# usb-gamepad.net
KiCad netlist of a schematic drawn in EAGLE
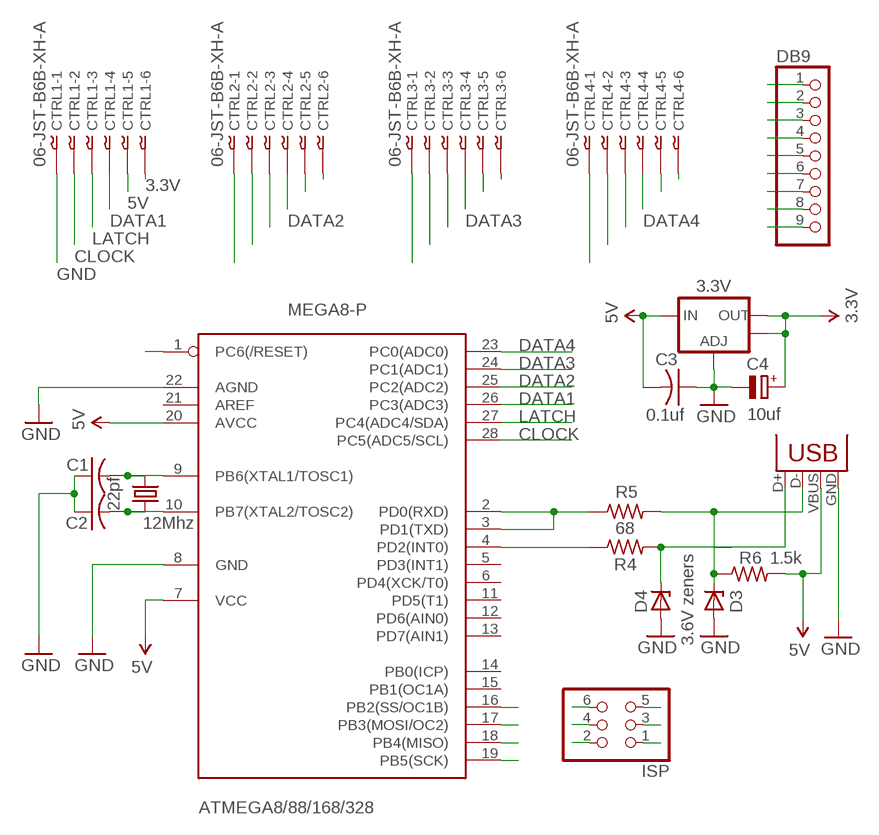
[diagram p0: schematic, sheet 1]

(export (version "E")
  (design (tool "Eeschema 10.0.6"))
  (components
    (comp (ref "3.3V")
      (value "V_REG_LM1117SOT223")
      (footprint "eagle-import:SOT223")
      (libsource (lib "eagle-import") (part "V_REG_LM1117SOT223"))
    )
    (comp (ref "ATMEGA8/88/168/328")
      (value "MEGA8-P")
      (footprint "eagle-import:DIL28-3")
      (libsource (lib "eagle-import") (part "MEGA8-P"))
    )
    (comp (ref "C1")
      (value "22pf")
      (footprint "eagle-import:C025-025X050")
      (libsource (lib "eagle-import") (part "C-US025-025X050"))
    )
    (comp (ref "C2")
      (value "22pf")
      (footprint "eagle-import:C025-025X050")
      (libsource (lib "eagle-import") (part "C-US025-025X050"))
    )
    (comp (ref "C3")
      (value "0.1uf")
      (footprint "eagle-import:C025-025X050")
      (libsource (lib "eagle-import") (part "C-US025-025X050"))
    )
    (comp (ref "C4")
      (value "10uf")
      (footprint "eagle-import:E2,5-5")
      (libsource (lib "eagle-import") (part "CPOL-EUE2.5-5"))
    )
    (comp (ref "CTRL1")
      (value "06-JST-B6B-XH-A")
      (footprint "eagle-import:B6B-XH")
      (libsource (lib "eagle-import") (part "06-JST-B6B-XH-A"))
    )
    (comp (ref "CTRL2")
      (value "06-JST-B6B-XH-A")
      (footprint "eagle-import:B6B-XH")
      (libsource (lib "eagle-import") (part "06-JST-B6B-XH-A"))
    )
    (comp (ref "CTRL3")
      (value "06-JST-B6B-XH-A")
      (footprint "eagle-import:B6B-XH")
      (libsource (lib "eagle-import") (part "06-JST-B6B-XH-A"))
    )
    (comp (ref "CTRL4")
      (value "06-JST-B6B-XH-A")
      (footprint "eagle-import:B6B-XH")
      (libsource (lib "eagle-import") (part "06-JST-B6B-XH-A"))
    )
    (comp (ref "D3")
      (value "3.6V zeners")
      (footprint "eagle-import:DO41Z10")
      (libsource (lib "eagle-import") (part "1N4728"))
    )
    (comp (ref "D4")
      (value "3.6V")
      (footprint "eagle-import:DO41Z10")
      (libsource (lib "eagle-import") (part "1N4728"))
    )
    (comp (ref "DB9")
      (value "PINHD-1X9")
      (footprint "eagle-import:1X09")
      (libsource (lib "eagle-import") (part "PINHD-1X9"))
    )
    (comp (ref "ISP")
      (value "PINHD-2X3")
      (footprint "eagle-import:2X03")
      (libsource (lib "eagle-import") (part "PINHD-2X3"))
    )
    (comp (ref "Q1")
      (value "12Mhz")
      (footprint "eagle-import:HC49_S")
      (libsource (lib "eagle-import") (part "CRYSTALHC49S"))
    )
    (comp (ref "R4")
      (value "68")
      (footprint "eagle-import:0207_10")
      (libsource (lib "eagle-import") (part "R-US_0207/10"))
    )
    (comp (ref "R5")
      (value "68")
      (footprint "eagle-import:0207_10")
      (libsource (lib "eagle-import") (part "R-US_0207/10"))
    )
    (comp (ref "R6")
      (value "1.5k")
      (footprint "eagle-import:0207_10")
      (libsource (lib "eagle-import") (part "R-US_0207/10"))
    )
    (comp (ref "USB")
      (value "USBPTH")
      (footprint "eagle-import:USB-B-PTH")
      (libsource (lib "eagle-import") (part "USBPTH"))
    )
  )
  (nets
    (net (code "1") (name "/CLOCK") (class "Default")
      (node (ref "ATMEGA8/88/168/328") (pin "28") (pinfunction "PC5(ADC5/SCL)_28") (pintype "bidirectional"))
      (node (ref "CTRL1") (pin "P$2") (pinfunction "1_P$2") (pintype "passive"))
      (node (ref "CTRL2") (pin "P$2") (pinfunction "1_P$2") (pintype "passive"))
      (node (ref "CTRL3") (pin "P$2") (pinfunction "1_P$2") (pintype "passive"))
      (node (ref "CTRL4") (pin "P$2") (pinfunction "1_P$2") (pintype "passive"))
      (node (ref "DB9") (pin "1") (pinfunction "1_1") (pintype "passive"))
    )
    (net (code "2") (name "/DATA1") (class "Default")
      (node (ref "ATMEGA8/88/168/328") (pin "26") (pinfunction "PC3(ADC3)_26") (pintype "bidirectional"))
      (node (ref "CTRL1") (pin "P$4") (pinfunction "1_P$4") (pintype "passive"))
      (node (ref "DB9") (pin "3") (pinfunction "3_3") (pintype "passive"))
    )
    (net (code "3") (name "/DATA2") (class "Default")
      (node (ref "ATMEGA8/88/168/328") (pin "25") (pinfunction "PC2(ADC2)_25") (pintype "bidirectional"))
      (node (ref "CTRL2") (pin "P$4") (pinfunction "1_P$4") (pintype "passive"))
      (node (ref "DB9") (pin "4") (pinfunction "4_4") (pintype "passive"))
    )
    (net (code "4") (name "/DATA3") (class "Default")
      (node (ref "ATMEGA8/88/168/328") (pin "24") (pinfunction "PC1(ADC1)_24") (pintype "bidirectional"))
      (node (ref "CTRL3") (pin "P$4") (pinfunction "1_P$4") (pintype "passive"))
      (node (ref "DB9") (pin "6") (pinfunction "6_6") (pintype "passive"))
    )
    (net (code "5") (name "/DATA4") (class "Default")
      (node (ref "ATMEGA8/88/168/328") (pin "23") (pinfunction "PC0(ADC0)_23") (pintype "bidirectional"))
      (node (ref "CTRL4") (pin "P$4") (pinfunction "1_P$4") (pintype "passive"))
      (node (ref "DB9") (pin "7") (pinfunction "7_7") (pintype "passive"))
    )
    (net (code "6") (name "/LATCH") (class "Default")
      (node (ref "ATMEGA8/88/168/328") (pin "27") (pinfunction "PC4(ADC4/SDA)_27") (pintype "bidirectional"))
      (node (ref "CTRL1") (pin "P$3") (pinfunction "1_P$3") (pintype "passive"))
      (node (ref "CTRL2") (pin "P$3") (pinfunction "1_P$3") (pintype "passive"))
      (node (ref "CTRL3") (pin "P$3") (pinfunction "1_P$3") (pintype "passive"))
      (node (ref "CTRL4") (pin "P$3") (pinfunction "1_P$3") (pintype "passive"))
      (node (ref "DB9") (pin "2") (pinfunction "2_2") (pintype "passive"))
    )
    (net (code "7") (name "/MISO") (class "Default")
      (node (ref "ATMEGA8/88/168/328") (pin "18") (pinfunction "PB4(MISO)_18") (pintype "bidirectional"))
      (node (ref "ISP") (pin "1") (pinfunction "1_1") (pintype "passive"))
    )
    (net (code "8") (name "/MOSI") (class "Default")
      (node (ref "ATMEGA8/88/168/328") (pin "17") (pinfunction "PB3(MOSI/OC2)_17") (pintype "bidirectional"))
      (node (ref "ISP") (pin "4") (pinfunction "4_4") (pintype "passive"))
    )
    (net (code "9") (name "/RESET") (class "Default")
      (node (ref "ATMEGA8/88/168/328") (pin "1") (pinfunction "PC6(/RESET)_1") (pintype "bidirectional"))
      (node (ref "ISP") (pin "5") (pinfunction "5_5") (pintype "passive"))
    )
    (net (code "10") (name "/SCK") (class "Default")
      (node (ref "ATMEGA8/88/168/328") (pin "19") (pinfunction "PB5(SCK)_19") (pintype "bidirectional"))
      (node (ref "DB9") (pin "9") (pinfunction "9_9") (pintype "passive"))
      (node (ref "ISP") (pin "3") (pinfunction "3_3") (pintype "passive"))
    )
    (net (code "11") (name "3.3V") (class "Default")
      (node (ref "3.3V") (pin "2") (pinfunction "OUT_2") (pintype "output"))
      (node (ref "3.3V") (pin "4") (pinfunction "OUT_4") (pintype "output"))
      (node (ref "C4") (pin "+") (pinfunction "+_+") (pintype "passive"))
      (node (ref "CTRL1") (pin "P$6") (pinfunction "1_P$6") (pintype "passive"))
      (node (ref "CTRL2") (pin "P$6") (pinfunction "1_P$6") (pintype "passive"))
      (node (ref "CTRL3") (pin "P$6") (pinfunction "1_P$6") (pintype "passive"))
      (node (ref "CTRL4") (pin "P$6") (pinfunction "1_P$6") (pintype "passive"))
    )
    (net (code "12") (name "5V") (class "Default")
      (node (ref "3.3V") (pin "3") (pinfunction "IN_3") (pintype "input"))
      (node (ref "ATMEGA8/88/168/328") (pin "20") (pinfunction "AVCC_20") (pintype "power_in"))
      (node (ref "ATMEGA8/88/168/328") (pin "7") (pinfunction "VCC_7") (pintype "power_in"))
      (node (ref "C3") (pin "2") (pinfunction "2_2") (pintype "passive"))
      (node (ref "CTRL1") (pin "P$5") (pinfunction "1_P$5") (pintype "passive"))
      (node (ref "CTRL2") (pin "P$5") (pinfunction "1_P$5") (pintype "passive"))
      (node (ref "CTRL3") (pin "P$5") (pinfunction "1_P$5") (pintype "passive"))
      (node (ref "CTRL4") (pin "P$5") (pinfunction "1_P$5") (pintype "passive"))
      (node (ref "DB9") (pin "5") (pinfunction "5_5") (pintype "passive"))
      (node (ref "ISP") (pin "2") (pinfunction "2_2") (pintype "passive"))
      (node (ref "R6") (pin "2") (pinfunction "2_2") (pintype "passive"))
      (node (ref "USB") (pin "VBUS") (pinfunction "VBUS_VBUS") (pintype "bidirectional"))
    )
    (net (code "13") (name "GND") (class "Default")
      (node (ref "3.3V") (pin "1") (pinfunction "ADJ_1") (pintype "input"))
      (node (ref "ATMEGA8/88/168/328") (pin "22") (pinfunction "AGND_22") (pintype "power_in"))
      (node (ref "ATMEGA8/88/168/328") (pin "8") (pinfunction "GND_8") (pintype "power_in"))
      (node (ref "C1") (pin "1") (pinfunction "1_1") (pintype "passive"))
      (node (ref "C2") (pin "1") (pinfunction "1_1") (pintype "passive"))
      (node (ref "C3") (pin "1") (pinfunction "1_1") (pintype "passive"))
      (node (ref "C4") (pin "-") (pinfunction "-_-") (pintype "passive"))
      (node (ref "CTRL1") (pin "P$1") (pinfunction "1_P$1") (pintype "passive"))
      (node (ref "CTRL2") (pin "P$1") (pinfunction "1_P$1") (pintype "passive"))
      (node (ref "CTRL3") (pin "P$1") (pinfunction "1_P$1") (pintype "passive"))
      (node (ref "CTRL4") (pin "P$1") (pinfunction "1_P$1") (pintype "passive"))
      (node (ref "D3") (pin "A") (pinfunction "A_A") (pintype "passive"))
      (node (ref "D4") (pin "A") (pinfunction "A_A") (pintype "passive"))
      (node (ref "DB9") (pin "8") (pinfunction "8_8") (pintype "passive"))
      (node (ref "ISP") (pin "6") (pinfunction "6_6") (pintype "passive"))
      (node (ref "USB") (pin "GND") (pinfunction "GND_GND") (pintype "bidirectional"))
    )
    (net (code "14") (name "Net-(ATMEGA8/88/168/328-PB6(XTAL1{slash}TOSC1))") (class "Default")
      (node (ref "ATMEGA8/88/168/328") (pin "9") (pinfunction "PB6(XTAL1/TOSC1)_9") (pintype "bidirectional"))
      (node (ref "C1") (pin "2") (pinfunction "2_2") (pintype "passive"))
      (node (ref "Q1") (pin "2") (pinfunction "2_2") (pintype "passive"))
    )
    (net (code "15") (name "Net-(ATMEGA8/88/168/328-PB7(XTAL2{slash}TOSC2))") (class "Default")
      (node (ref "ATMEGA8/88/168/328") (pin "10") (pinfunction "PB7(XTAL2/TOSC2)_10") (pintype "bidirectional"))
      (node (ref "C2") (pin "2") (pinfunction "2_2") (pintype "passive"))
      (node (ref "Q1") (pin "1") (pinfunction "1_1") (pintype "passive"))
    )
    (net (code "16") (name "Net-(ATMEGA8/88/168/328-PD0(RXD))") (class "Default")
      (node (ref "ATMEGA8/88/168/328") (pin "2") (pinfunction "PD0(RXD)_2") (pintype "bidirectional"))
      (node (ref "ATMEGA8/88/168/328") (pin "3") (pinfunction "PD1(TXD)_3") (pintype "bidirectional"))
      (node (ref "R5") (pin "1") (pinfunction "1_1") (pintype "passive"))
    )
    (net (code "17") (name "Net-(ATMEGA8/88/168/328-PD2(INT0))") (class "Default")
      (node (ref "ATMEGA8/88/168/328") (pin "4") (pinfunction "PD2(INT0)_4") (pintype "bidirectional"))
      (node (ref "R4") (pin "1") (pinfunction "1_1") (pintype "passive"))
    )
    (net (code "18") (name "Net-(D3-PadC)") (class "Default")
      (node (ref "D3") (pin "C") (pinfunction "C_C") (pintype "passive"))
      (node (ref "R5") (pin "2") (pinfunction "2_2") (pintype "passive"))
      (node (ref "R6") (pin "1") (pinfunction "1_1") (pintype "passive"))
      (node (ref "USB") (pin "D-") (pinfunction "D-_D-") (pintype "bidirectional"))
    )
    (net (code "19") (name "Net-(D4-PadC)") (class "Default")
      (node (ref "D4") (pin "C") (pinfunction "C_C") (pintype "passive"))
      (node (ref "R4") (pin "2") (pinfunction "2_2") (pintype "passive"))
      (node (ref "USB") (pin "D+") (pinfunction "D+_D+") (pintype "bidirectional"))
    )
    (net (code "20") (name "unconnected-(ATMEGA8/88/168/328-AREF-Pad21)") (class "Default")
      (node (ref "ATMEGA8/88/168/328") (pin "21") (pinfunction "AREF_21") (pintype "passive"))
    )
    (net (code "21") (name "unconnected-(ATMEGA8/88/168/328-PB0(ICP)-Pad14)") (class "Default")
      (node (ref "ATMEGA8/88/168/328") (pin "14") (pinfunction "PB0(ICP)_14") (pintype "bidirectional"))
    )
    (net (code "22") (name "unconnected-(ATMEGA8/88/168/328-PB1(OC1A)-Pad15)") (class "Default")
      (node (ref "ATMEGA8/88/168/328") (pin "15") (pinfunction "PB1(OC1A)_15") (pintype "bidirectional"))
    )
    (net (code "23") (name "unconnected-(ATMEGA8/88/168/328-PB2(SS{slash}OC1B)-Pad16)") (class "Default")
      (node (ref "ATMEGA8/88/168/328") (pin "16") (pinfunction "PB2(SS/OC1B)_16") (pintype "bidirectional"))
    )
    (net (code "24") (name "unconnected-(ATMEGA8/88/168/328-PD3(INT1)-Pad5)") (class "Default")
      (node (ref "ATMEGA8/88/168/328") (pin "5") (pinfunction "PD3(INT1)_5") (pintype "bidirectional"))
    )
    (net (code "25") (name "unconnected-(ATMEGA8/88/168/328-PD4(XCK{slash}T0)-Pad6)") (class "Default")
      (node (ref "ATMEGA8/88/168/328") (pin "6") (pinfunction "PD4(XCK/T0)_6") (pintype "bidirectional"))
    )
    (net (code "26") (name "unconnected-(ATMEGA8/88/168/328-PD5(T1)-Pad11)") (class "Default")
      (node (ref "ATMEGA8/88/168/328") (pin "11") (pinfunction "PD5(T1)_11") (pintype "bidirectional"))
    )
    (net (code "27") (name "unconnected-(ATMEGA8/88/168/328-PD6(AIN0)-Pad12)") (class "Default")
      (node (ref "ATMEGA8/88/168/328") (pin "12") (pinfunction "PD6(AIN0)_12") (pintype "bidirectional"))
    )
    (net (code "28") (name "unconnected-(ATMEGA8/88/168/328-PD7(AIN1)-Pad13)") (class "Default")
      (node (ref "ATMEGA8/88/168/328") (pin "13") (pinfunction "PD7(AIN1)_13") (pintype "bidirectional"))
    )
  )
)
